# Module_AFE.net
KiCad netlist of a schematic drawn in Altium Designer
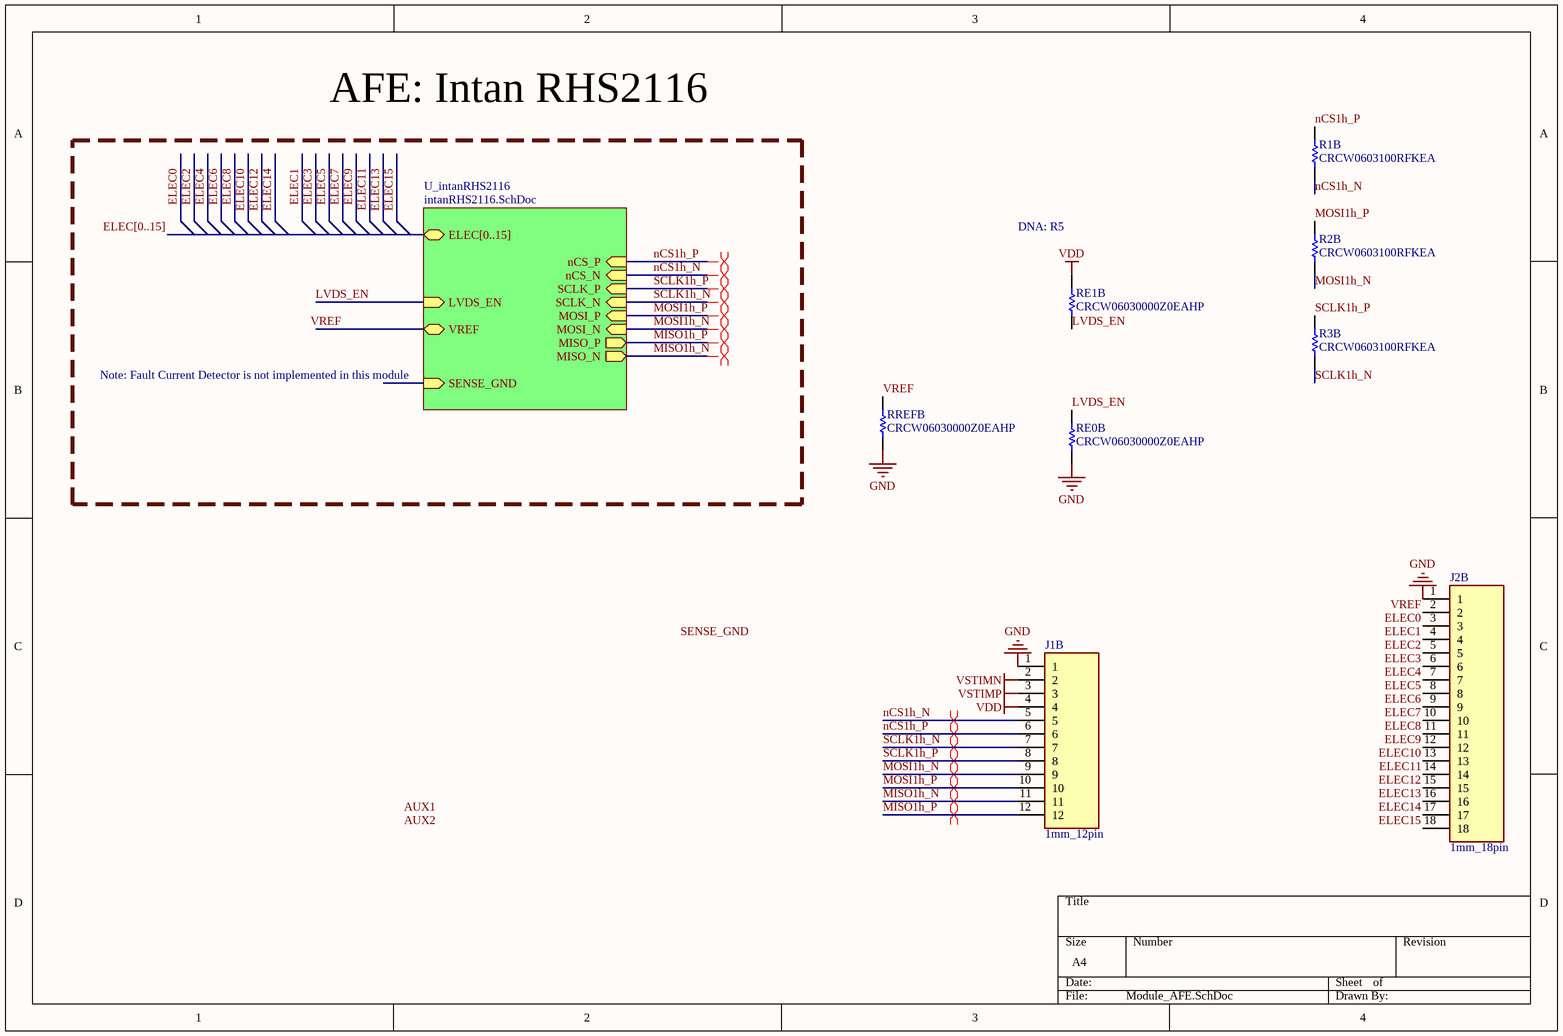
[diagram p0: Module_AFE.SchDoc]

(export (version "E")
  (design (tool "Eeschema 10.0.6"))
  (components
    (comp (ref "J1B")
      (value "1mm_12pin")
      (footprint "1mm_12pin")
      (libsource (lib "intan_rhs2116_breakout") (part "1mm_12pin"))
    )
    (comp (ref "J2B")
      (value "1mm_18pin")
      (footprint "1mm_18pin")
      (libsource (lib "ANIMO_V001") (part "1mm_18pin"))
    )
    (comp (ref "R1B")
      (value "CRCW0603100RFKEA")
      (footprint "RESC1609X50X30ML8T20")
      (description "Chip Resistor, 100 Ohm, +/- 1%, 100 mW,-55 to 155 degC, 0603 (1608 Metric), RoHS, Tape and Ree")
      (fields (field (name "MANUFACTURER") "Vishay Semiconductor"))
      (libsource (lib "Altium Content Vault") (part "RES-2"))
    )
    (comp (ref "R2B")
      (value "CRCW0603100RFKEA")
      (footprint "RESC1609X50X30ML8T20")
      (description "Chip Resistor, 100 Ohm, +/- 1%, 100 mW,-55 to 155 degC, 0603 (1608 Metric), RoHS, Tape and Ree")
      (fields (field (name "MANUFACTURER") "Vishay Semiconductor"))
      (libsource (lib "Altium Content Vault") (part "RES-2"))
    )
    (comp (ref "R3B")
      (value "CRCW0603100RFKEA")
      (footprint "RESC1609X50X30ML8T20")
      (description "Chip Resistor, 100 Ohm, +/- 1%, 100 mW,-55 to 155 degC, 0603 (1608 Metric), RoHS, Tape and Ree")
      (fields (field (name "MANUFACTURER") "Vishay Semiconductor"))
      (libsource (lib "Altium Content Vault") (part "RES-2"))
    )
    (comp (ref "RE0B")
      (value "CRCW06030000Z0EAHP")
      (footprint "RESC1609X55X30NL10T20")
      (fields (field (name "MANUFACTURER") "Vishay Dale"))
      (libsource (lib "Altium Content Vault") (part "RES"))
    )
    (comp (ref "RE1B")
      (value "CRCW06030000Z0EAHP")
      (footprint "RESC1609X55X30NL10T20")
      (fields (field (name "MANUFACTURER") "Vishay Dale"))
      (libsource (lib "Altium Content Vault") (part "RES"))
    )
    (comp (ref "RREFB")
      (value "CRCW06030000Z0EAHP")
      (footprint "RESC1609X55X30NL10T20")
      (fields (field (name "MANUFACTURER") "Vishay Dale"))
      (libsource (lib "Altium Content Vault") (part "RES"))
    )
  )
  (nets
    (net (code "3") (name "/ELEC0") (class "Default")
      (node (ref "J2B") (pin "3") (pinfunction "3_3") (pintype "passive"))
    )
    (net (code "4") (name "/ELEC1") (class "Default")
      (node (ref "J2B") (pin "4") (pinfunction "4_4") (pintype "passive"))
    )
    (net (code "5") (name "/ELEC2") (class "Default")
      (node (ref "J2B") (pin "5") (pinfunction "5_5") (pintype "passive"))
    )
    (net (code "6") (name "/ELEC3") (class "Default")
      (node (ref "J2B") (pin "6") (pinfunction "6_6") (pintype "passive"))
    )
    (net (code "7") (name "/ELEC4") (class "Default")
      (node (ref "J2B") (pin "7") (pinfunction "7_7") (pintype "passive"))
    )
    (net (code "8") (name "/ELEC5") (class "Default")
      (node (ref "J2B") (pin "8") (pinfunction "8_8") (pintype "passive"))
    )
    (net (code "9") (name "/ELEC6") (class "Default")
      (node (ref "J2B") (pin "9") (pinfunction "9_9") (pintype "passive"))
    )
    (net (code "10") (name "/ELEC7") (class "Default")
      (node (ref "J2B") (pin "10") (pinfunction "10_10") (pintype "passive"))
    )
    (net (code "11") (name "/ELEC8") (class "Default")
      (node (ref "J2B") (pin "11") (pinfunction "11_11") (pintype "passive"))
    )
    (net (code "12") (name "/ELEC9") (class "Default")
      (node (ref "J2B") (pin "12") (pinfunction "12_12") (pintype "passive"))
    )
    (net (code "13") (name "/ELEC10") (class "Default")
      (node (ref "J2B") (pin "13") (pinfunction "13_13") (pintype "passive"))
    )
    (net (code "14") (name "/ELEC11") (class "Default")
      (node (ref "J2B") (pin "14") (pinfunction "14_14") (pintype "passive"))
    )
    (net (code "15") (name "/ELEC12") (class "Default")
      (node (ref "J2B") (pin "15") (pinfunction "15_15") (pintype "passive"))
    )
    (net (code "16") (name "/ELEC13") (class "Default")
      (node (ref "J2B") (pin "16") (pinfunction "16_16") (pintype "passive"))
    )
    (net (code "17") (name "/ELEC14") (class "Default")
      (node (ref "J2B") (pin "17") (pinfunction "17_17") (pintype "passive"))
    )
    (net (code "18") (name "/ELEC15") (class "Default")
      (node (ref "J2B") (pin "18") (pinfunction "18_18") (pintype "passive"))
    )
    (net (code "20") (name "/LVDS_EN") (class "Default")
      (node (ref "RE0B") (pin "2") (pinfunction "2_2") (pintype "passive"))
      (node (ref "RE1B") (pin "1") (pinfunction "1_1") (pintype "passive"))
    )
    (net (code "21") (name "/MISO1h_N") (class "Default")
      (node (ref "J1B") (pin "11") (pinfunction "11_11") (pintype "passive"))
    )
    (net (code "22") (name "/MISO1h_P") (class "Default")
      (node (ref "J1B") (pin "12") (pinfunction "12_12") (pintype "passive"))
    )
    (net (code "23") (name "/MOSI1h_N") (class "Default")
      (node (ref "J1B") (pin "9") (pinfunction "9_9") (pintype "passive"))
      (node (ref "R2B") (pin "1") (pinfunction "1_1") (pintype "passive"))
    )
    (net (code "24") (name "/MOSI1h_P") (class "Default")
      (node (ref "J1B") (pin "10") (pinfunction "10_10") (pintype "passive"))
      (node (ref "R2B") (pin "2") (pinfunction "2_2") (pintype "passive"))
    )
    (net (code "25") (name "/SCLK1h_N") (class "Default")
      (node (ref "J1B") (pin "7") (pinfunction "7_7") (pintype "passive"))
      (node (ref "R3B") (pin "1") (pinfunction "1_1") (pintype "passive"))
    )
    (net (code "26") (name "/SCLK1h_P") (class "Default")
      (node (ref "J1B") (pin "8") (pinfunction "8_8") (pintype "passive"))
      (node (ref "R3B") (pin "2") (pinfunction "2_2") (pintype "passive"))
    )
    (net (code "29") (name "/VREF") (class "Default")
      (node (ref "J2B") (pin "2") (pinfunction "2_2") (pintype "passive"))
      (node (ref "RREFB") (pin "2") (pinfunction "2_2") (pintype "passive"))
    )
    (net (code "30") (name "/nCS1h_N") (class "Default")
      (node (ref "J1B") (pin "5") (pinfunction "5_5") (pintype "passive"))
      (node (ref "R1B") (pin "1") (pinfunction "1_1") (pintype "passive"))
    )
    (net (code "31") (name "/nCS1h_P") (class "Default")
      (node (ref "J1B") (pin "6") (pinfunction "6_6") (pintype "passive"))
      (node (ref "R1B") (pin "2") (pinfunction "2_2") (pintype "passive"))
    )
    (net (code "32") (name "GND") (class "Default")
      (node (ref "J1B") (pin "1") (pinfunction "1_1") (pintype "passive"))
      (node (ref "J2B") (pin "1") (pinfunction "1_1") (pintype "passive"))
      (node (ref "RE0B") (pin "1") (pinfunction "1_1") (pintype "passive"))
      (node (ref "RREFB") (pin "1") (pinfunction "1_1") (pintype "passive"))
    )
    (net (code "33") (name "VDD") (class "Default")
      (node (ref "J1B") (pin "4") (pinfunction "4_4") (pintype "passive"))
      (node (ref "RE1B") (pin "2") (pinfunction "2_2") (pintype "passive"))
    )
    (net (code "34") (name "VSTIMN") (class "Default")
      (node (ref "J1B") (pin "2") (pinfunction "2_2") (pintype "passive"))
    )
    (net (code "35") (name "VSTIMP") (class "Default")
      (node (ref "J1B") (pin "3") (pinfunction "3_3") (pintype "passive"))
    )
  )
)
